# PATHOS_AnalogOut.net
KiCad netlist of a schematic drawn in Altium Designer
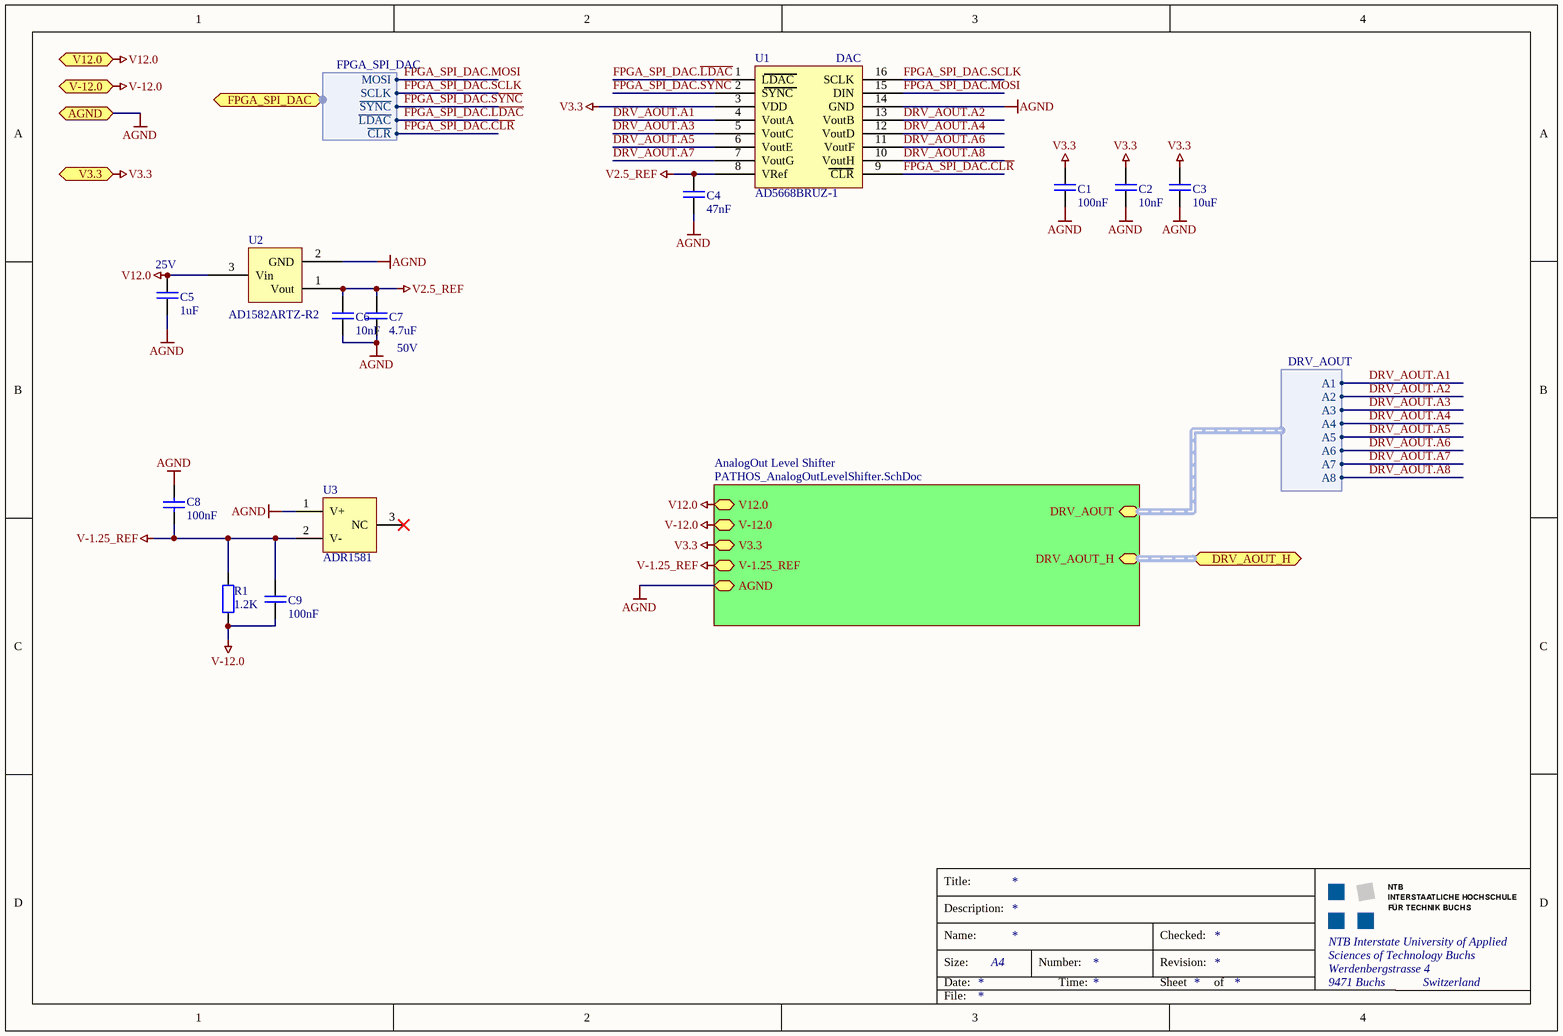
[diagram p0: PATHOS_AnalogOut.SchDoc]

(export (version "E")
  (design (tool "Eeschema 10.0.6"))
  (components
    (comp (ref "C1")
      (value "100nF")
      (footprint "0603_3D")
      (description "Capacitor")
      (fields (field (name "#PUBLISHER") "Dr. A. Heinzelmann"))
      (libsource (lib "PartLib") (part "C"))
    )
    (comp (ref "C2")
      (value "10nF")
      (footprint "0603_3D")
      (description "Capacitor")
      (fields (field (name "#PUBLISHER") "Dr. A. Heinzelmann"))
      (libsource (lib "PartLib") (part "C"))
    )
    (comp (ref "C3")
      (value "10uF")
      (footprint "0603_3D")
      (description "Capacitor")
      (fields (field (name "#PUBLISHER") "Dr. A. Heinzelmann"))
      (libsource (lib "PartLib") (part "C"))
    )
    (comp (ref "C4")
      (value "47nF")
      (footprint "0603_3D")
      (description "Capacitor")
      (fields (field (name "#PUBLISHER") "Dr. A. Heinzelmann"))
      (libsource (lib "PartLib") (part "C"))
    )
    (comp (ref "C5")
      (value "1uF")
      (footprint "0603_3D")
      (description "Capacitor")
      (fields (field (name "VOLTAGE MAXIMUM") "25V") (field (name "#PUBLISHER") "Dr. A. Heinzelmann"))
      (libsource (lib "PartLib") (part "C"))
    )
    (comp (ref "C6")
      (value "10nF")
      (footprint "0603_3D")
      (description "Capacitor")
      (fields (field (name "#PUBLISHER") "Dr. A. Heinzelmann"))
      (libsource (lib "PartLib") (part "C"))
    )
    (comp (ref "C7")
      (value "4.7uF")
      (footprint "1206")
      (description "Capacitor")
      (fields (field (name "VOLTAGE MAXIMUM") "50V") (field (name "#PUBLISHER") "Dr. A. Heinzelmann"))
      (libsource (lib "PartLib") (part "C"))
    )
    (comp (ref "C8")
      (value "100nF")
      (footprint "0603_3D")
      (description "Capacitor")
      (fields (field (name "#PUBLISHER") "Dr. A. Heinzelmann"))
      (libsource (lib "ELE-LIB") (part "C"))
    )
    (comp (ref "C9")
      (value "100nF")
      (footprint "0603_3D")
      (description "Capacitor")
      (fields (field (name "#PUBLISHER") "Dr. A. Heinzelmann"))
      (libsource (lib "PartLib") (part "C"))
    )
    (comp (ref "R1")
      (value "1.2K")
      (footprint "0603")
      (description "Resistor")
      (fields (field (name "#PUBLISHER") "Dr. A. Heinzelmann"))
      (libsource (lib "PartLib") (part "R"))
    )
    (comp (ref "U1")
      (value "AD5668BRUZ-1")
      (footprint "TSSOP16-W")
      (libsource (lib "PartLib") (part "AD5668BRUZ-1"))
    )
    (comp (ref "U2")
      (value "AD1582ARTZ-R2")
      (footprint "SOT23")
      (libsource (lib "PartLib") (part "AD1582ARTZ-R2"))
    )
    (comp (ref "U3") (value "ADR1581") (footprint "SOT23") (libsource (lib "PartLib") (part "ADR1581")))
  )
  (nets
    (net (code "4") (name "/DRV_AOUT.A1") (class "Default")
      (node (ref "U1") (pin "4") (pinfunction "VoutA_4") (pintype "passive"))
    )
    (net (code "5") (name "/DRV_AOUT.A2") (class "Default")
      (node (ref "U1") (pin "13") (pinfunction "VoutB_13") (pintype "passive"))
    )
    (net (code "6") (name "/DRV_AOUT.A3") (class "Default")
      (node (ref "U1") (pin "5") (pinfunction "VoutC_5") (pintype "passive"))
    )
    (net (code "7") (name "/DRV_AOUT.A4") (class "Default")
      (node (ref "U1") (pin "12") (pinfunction "VoutD_12") (pintype "passive"))
    )
    (net (code "8") (name "/DRV_AOUT.A5") (class "Default")
      (node (ref "U1") (pin "6") (pinfunction "VoutE_6") (pintype "passive"))
    )
    (net (code "9") (name "/DRV_AOUT.A6") (class "Default")
      (node (ref "U1") (pin "11") (pinfunction "VoutF_11") (pintype "passive"))
    )
    (net (code "10") (name "/DRV_AOUT.A7") (class "Default")
      (node (ref "U1") (pin "7") (pinfunction "VoutG_7") (pintype "passive"))
    )
    (net (code "11") (name "/DRV_AOUT.A8") (class "Default")
      (node (ref "U1") (pin "10") (pinfunction "VoutH_10") (pintype "passive"))
    )
    (net (code "13") (name "/FPGA_SPI_DAC.MOSI") (class "Default")
      (node (ref "U1") (pin "15") (pinfunction "DIN_15") (pintype "passive"))
    )
    (net (code "14") (name "/FPGA_SPI_DAC.SCLK") (class "Default")
      (node (ref "U1") (pin "16") (pinfunction "SCLK_16") (pintype "passive"))
    )
    (net (code "15") (name "/FPGA_SPI_DAC.~{CLR}") (class "Default")
      (node (ref "U1") (pin "9") (pinfunction "CLR_9") (pintype "passive"))
    )
    (net (code "16") (name "/FPGA_SPI_DAC.~{LDAC}") (class "Default")
      (node (ref "U1") (pin "1") (pinfunction "LDAC_1") (pintype "passive"))
    )
    (net (code "17") (name "/FPGA_SPI_DAC.~{SYNC}") (class "Default")
      (node (ref "U1") (pin "2") (pinfunction "SYNC_2") (pintype "passive"))
    )
    (net (code "20") (name "AGND") (class "Default")
      (node (ref "C1") (pin "2") (pinfunction "2_2") (pintype "passive"))
      (node (ref "C2") (pin "2") (pinfunction "2_2") (pintype "passive"))
      (node (ref "C3") (pin "2") (pinfunction "2_2") (pintype "passive"))
      (node (ref "C4") (pin "2") (pinfunction "2_2") (pintype "passive"))
      (node (ref "C5") (pin "1") (pinfunction "1_1") (pintype "passive"))
      (node (ref "C6") (pin "2") (pinfunction "2_2") (pintype "passive"))
      (node (ref "C7") (pin "2") (pinfunction "2_2") (pintype "passive"))
      (node (ref "C8") (pin "2") (pinfunction "2_2") (pintype "passive"))
      (node (ref "U1") (pin "14") (pinfunction "GND_14") (pintype "passive"))
      (node (ref "U2") (pin "2") (pinfunction "GND_2") (pintype "passive"))
      (node (ref "U3") (pin "1") (pinfunction "V+_1") (pintype "passive"))
    )
    (net (code "21") (name "V-1.25_REF") (class "Default")
      (node (ref "C8") (pin "1") (pinfunction "1_1") (pintype "passive"))
      (node (ref "C9") (pin "2") (pinfunction "2_2") (pintype "passive"))
      (node (ref "R1") (pin "2") (pinfunction "2_2") (pintype "passive"))
      (node (ref "U3") (pin "2") (pinfunction "V-_2") (pintype "passive"))
    )
    (net (code "22") (name "V-12.0") (class "Default")
      (node (ref "C9") (pin "1") (pinfunction "1_1") (pintype "passive"))
      (node (ref "R1") (pin "1") (pinfunction "1_1") (pintype "passive"))
    )
    (net (code "23") (name "V2.5_REF") (class "Default")
      (node (ref "C4") (pin "1") (pinfunction "1_1") (pintype "passive"))
      (node (ref "C6") (pin "1") (pinfunction "1_1") (pintype "passive"))
      (node (ref "C7") (pin "1") (pinfunction "1_1") (pintype "passive"))
      (node (ref "U1") (pin "8") (pinfunction "VRef_8") (pintype "passive"))
      (node (ref "U2") (pin "1") (pinfunction "Vout_1") (pintype "passive"))
    )
    (net (code "24") (name "V3.3") (class "Default")
      (node (ref "C1") (pin "1") (pinfunction "1_1") (pintype "passive"))
      (node (ref "C2") (pin "1") (pinfunction "1_1") (pintype "passive"))
      (node (ref "C3") (pin "1") (pinfunction "1_1") (pintype "passive"))
      (node (ref "U1") (pin "3") (pinfunction "VDD_3") (pintype "passive"))
    )
    (net (code "25") (name "V12.0") (class "Default")
      (node (ref "C5") (pin "2") (pinfunction "2_2") (pintype "passive"))
      (node (ref "U2") (pin "3") (pinfunction "Vin_3") (pintype "passive"))
    )
    (net (code "26") (name "unconnected-(U3-NC-Pad3)") (class "Default")
      (node (ref "U3") (pin "3") (pinfunction "NC_3") (pintype "passive+no_connect"))
    )
  )
)
